# Power.net
KiCad netlist of a schematic drawn in Altium Designer
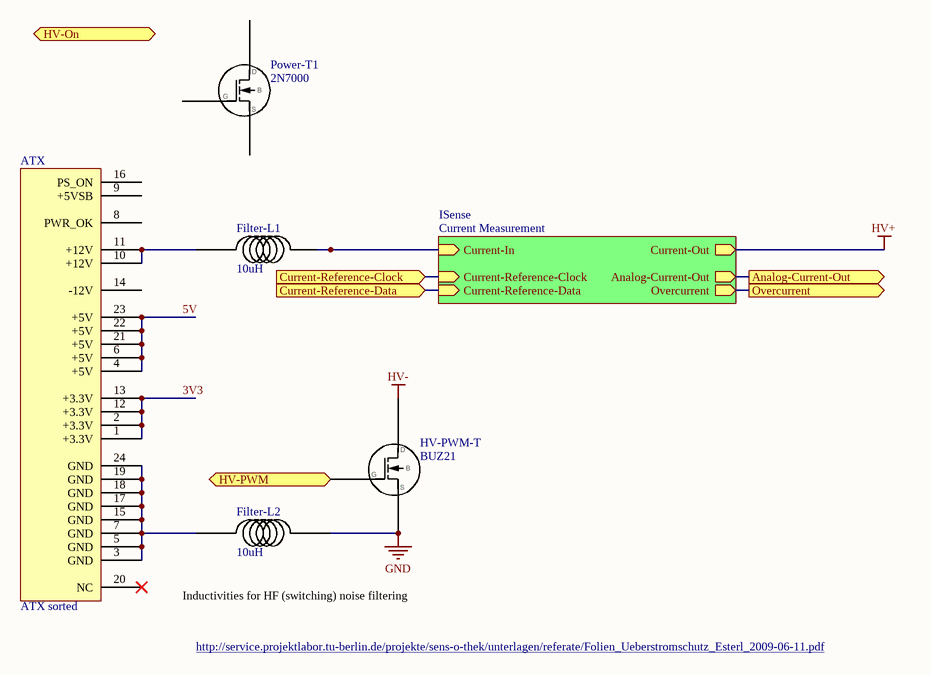
[diagram p0: Power.SchDoc]

(export (version "E")
  (design (tool "Eeschema 10.0.6"))
  (components
    (comp (ref "ATX")
      (value "ATX sorted")
      (footprint "ATX")
      (libsource (lib "Connectors") (part "ATX sorted"))
    )
    (comp (ref "Filter-L1")
      (value "10uH")
      (footprint "Header 1x2+1 1.0mm")
      (libsource (lib "Standard") (part "Coil"))
    )
    (comp (ref "Filter-L2")
      (value "10uH")
      (footprint "Header 1x2+1 1.0mm")
      (libsource (lib "Standard") (part "Coil"))
    )
    (comp (ref "HV-PWM-T")
      (value "BUZ21")
      (description "Enhancement Type")
      (libsource (lib "ICs") (part "FET N-Channel"))
    )
    (comp (ref "Power-T1")
      (value "2N7000")
      (footprint "SOT-23-3")
      (description "N-FET")
      (libsource (lib "ICs") (part "2N7000"))
    )
  )
  (nets
    (net (code "1") (name "/3V3") (class "Default")
      (node (ref "ATX") (pin "1") (pinfunction "+3.3V_1") (pintype "passive"))
      (node (ref "ATX") (pin "12") (pinfunction "+3.3V_12") (pintype "passive"))
      (node (ref "ATX") (pin "13") (pinfunction "+3.3V_13") (pintype "passive"))
      (node (ref "ATX") (pin "2") (pinfunction "+3.3V_2") (pintype "passive"))
    )
    (net (code "2") (name "/5V") (class "Default")
      (node (ref "ATX") (pin "21") (pinfunction "+5V_21") (pintype "passive"))
      (node (ref "ATX") (pin "22") (pinfunction "+5V_22") (pintype "passive"))
      (node (ref "ATX") (pin "23") (pinfunction "+5V_23") (pintype "passive"))
      (node (ref "ATX") (pin "4") (pinfunction "+5V_4") (pintype "passive"))
      (node (ref "ATX") (pin "6") (pinfunction "+5V_6") (pintype "passive"))
    )
    (net (code "4") (name "/Current-In") (class "Default")
      (node (ref "Filter-L1") (pin "2") (pinfunction "2_2") (pintype "passive"))
    )
    (net (code "8") (name "/HV-PWM") (class "Default")
      (node (ref "HV-PWM-T") (pin "G") (pinfunction "G_G") (pintype "passive"))
    )
    (net (code "10") (name "GND") (class "Default")
      (node (ref "Filter-L2") (pin "2") (pinfunction "2_2") (pintype "passive"))
      (node (ref "HV-PWM-T") (pin "S") (pinfunction "S_S") (pintype "passive"))
    )
    (net (code "12") (name "HV-") (class "Default")
      (node (ref "HV-PWM-T") (pin "D") (pinfunction "D_D") (pintype "passive"))
    )
    (net (code "13") (name "Net-(ATX-+12V-Pad10)") (class "Default")
      (node (ref "ATX") (pin "10") (pinfunction "+12V_10") (pintype "passive"))
      (node (ref "ATX") (pin "11") (pinfunction "+12V_11") (pintype "passive"))
      (node (ref "Filter-L1") (pin "1") (pinfunction "1_1") (pintype "passive"))
    )
    (net (code "14") (name "Net-(ATX-GND-Pad15)") (class "Default")
      (node (ref "ATX") (pin "15") (pinfunction "GND_15") (pintype "passive"))
      (node (ref "ATX") (pin "17") (pinfunction "GND_17") (pintype "passive"))
      (node (ref "ATX") (pin "18") (pinfunction "GND_18") (pintype "passive"))
      (node (ref "ATX") (pin "19") (pinfunction "GND_19") (pintype "passive"))
      (node (ref "ATX") (pin "24") (pinfunction "GND_24") (pintype "passive"))
      (node (ref "ATX") (pin "3") (pinfunction "GND_3") (pintype "passive"))
      (node (ref "ATX") (pin "5") (pinfunction "GND_5") (pintype "passive"))
      (node (ref "ATX") (pin "7") (pinfunction "GND_7") (pintype "passive"))
      (node (ref "Filter-L2") (pin "1") (pinfunction "1_1") (pintype "passive"))
    )
    (net (code "15") (name "unconnected-(ATX-+5VSB-Pad9)") (class "Default")
      (node (ref "ATX") (pin "9") (pinfunction "+5VSB_9") (pintype "passive"))
    )
    (net (code "16") (name "unconnected-(ATX--12V-Pad14)") (class "Default")
      (node (ref "ATX") (pin "14") (pinfunction "-12V_14") (pintype "passive"))
    )
    (net (code "17") (name "unconnected-(ATX-NC-Pad20)") (class "Default")
      (node (ref "ATX") (pin "20") (pinfunction "NC_20") (pintype "passive+no_connect"))
    )
    (net (code "18") (name "unconnected-(ATX-PS_ON-Pad16)") (class "Default")
      (node (ref "ATX") (pin "16") (pinfunction "PS_ON_16") (pintype "passive"))
    )
    (net (code "19") (name "unconnected-(ATX-PWR_OK-Pad8)") (class "Default")
      (node (ref "ATX") (pin "8") (pinfunction "PWR_OK_8") (pintype "passive"))
    )
    (net (code "20") (name "unconnected-(Power-T1-Pad1)") (class "Default")
      (node (ref "Power-T1") (pin "1") (pinfunction "1_1") (pintype "passive"))
    )
    (net (code "21") (name "unconnected-(Power-T1-Pad2)") (class "Default")
      (node (ref "Power-T1") (pin "2") (pinfunction "2_2") (pintype "passive"))
    )
    (net (code "22") (name "unconnected-(Power-T1-Pad3)") (class "Default")
      (node (ref "Power-T1") (pin "3") (pinfunction "3_3") (pintype "passive"))
    )
  )
)
